# Power_supply.net
KiCad netlist of a schematic drawn in Altium Designer
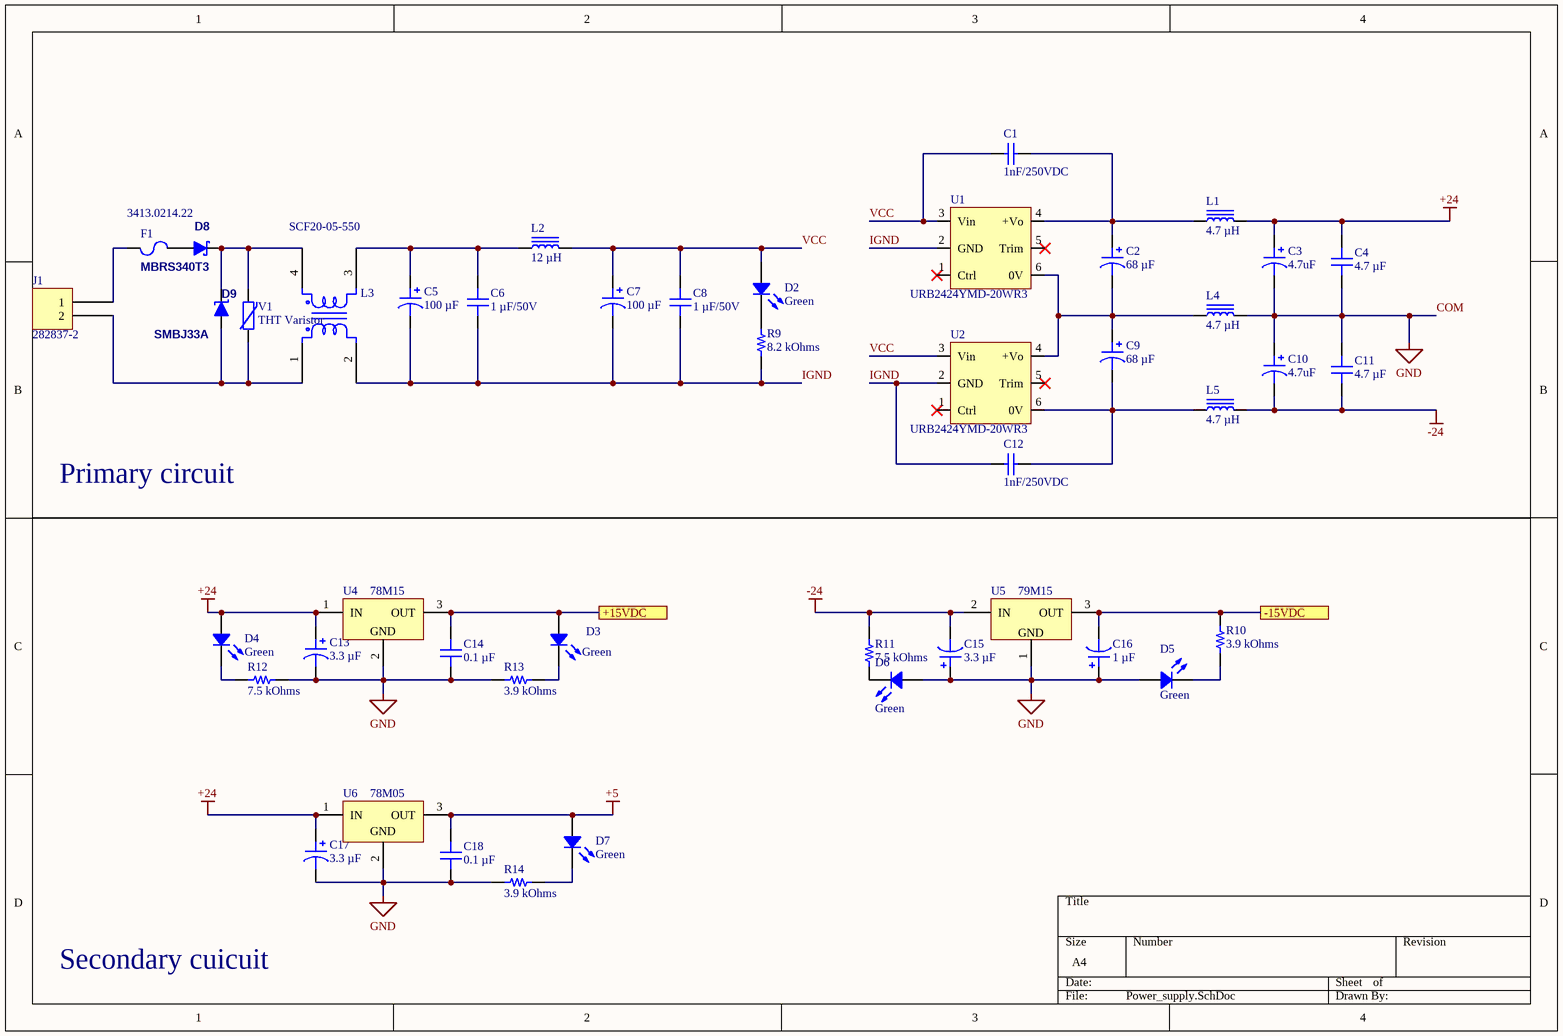
[diagram p0: Power_supply.SchDoc]

(export (version "E")
  (design (tool "Eeschema 10.0.6"))
  (components
    (comp (ref "C1")
      (value "1nF/250VDC")
      (footprint "SIOV-S07K11")
      (description "pitch 7.5 mm")
      (libsource (lib "Capacitor") (part "Y safety capacitor"))
    )
    (comp (ref "C2")
      (value "68 µF")
      (footprint "CAP ALSMD 8.3MM H10.5MM")
      (description "CAP ALUM 68UF 20% 50V SMD")
      (fields (field (name "PART NUMBER") "865060653009") (field (name "MANUFACTURER") "Würth Elektronik"))
      (libsource (lib "Celestial Altium Library - altium_library") (part "Polarised Capacitor"))
    )
    (comp (ref "C3")
      (value "4.7uF")
      (footprint "CAP ALSMD 8.3MM H10.5MM")
      (description "CAP ALUM 47UF 20% 50V SMD")
      (fields (field (name "PART NUMBER") "UCX1H470MCS1GS") (field (name "MANUFACTURER") "Nichicon"))
      (libsource (lib "Celestial Altium Library - altium_library") (part "Polarised Capacitor"))
    )
    (comp (ref "C4")
      (value "4.7 µF")
      (footprint "CAP 1210_3225 - 1MM")
      (description "CAP 1210 X7R 100V 4.7UF 10% 2.50")
      (fields
        (field (name "PART NUMBER") "CNC6P1X7R2A475K250AE")
        (field (name "MANUFACTURER") "TDK Corporation")
      )
      (libsource (lib "Celestial Altium Library - altium_library") (part "Capacitor"))
    )
    (comp (ref "C5")
      (value "100 µF")
      (footprint "CAP ALSMD 8.3MM H10.5MM")
      (description "CAP ALUM 100UF 20% 50V SMD")
      (fields (field (name "PART NUMBER") "UWT1H101MNL1GS") (field (name "MANUFACTURER") "Nichicon"))
      (libsource (lib "Celestial Altium Library - altium_library") (part "Polarised Capacitor"))
    )
    (comp (ref "C6")
      (value "4.7 µF")
      (footprint "CAP 1206_3216 - 0.8MM")
      (description "CAP CER 4.7UF 100V X7S 1206")
      (fields
        (field (name "PART NUMBER") "GRM31CC72A475KE11K")
        (field (name "CAPACITANCE") "1 µF/50V")
        (field (name "MANUFACTURER") "Murata Electronics")
      )
      (libsource (lib "Celestial Altium Library - altium_library") (part "Capacitor"))
    )
    (comp (ref "C7")
      (value "100 µF")
      (footprint "CAP ALSMD 8.3MM H10.5MM")
      (description "CAP ALUM 100UF 20% 50V SMD")
      (fields (field (name "PART NUMBER") "UWT1H101MNL1GS") (field (name "MANUFACTURER") "Nichicon"))
      (libsource (lib "Celestial Altium Library - altium_library") (part "Polarised Capacitor"))
    )
    (comp (ref "C8")
      (value "4.7 µF")
      (footprint "CAP 1206_3216 - 0.8MM")
      (description "CAP CER 4.7UF 100V X7S 1206")
      (fields
        (field (name "PART NUMBER") "GRM31CC72A475KE11K")
        (field (name "CAPACITANCE") "1 µF/50V")
        (field (name "MANUFACTURER") "Murata Electronics")
      )
      (libsource (lib "Celestial Altium Library - altium_library") (part "Capacitor"))
    )
    (comp (ref "C9")
      (value "68 µF")
      (footprint "CAP ALSMD 8.3MM H10.5MM")
      (description "CAP ALUM 68UF 20% 50V SMD")
      (fields (field (name "PART NUMBER") "865060653009") (field (name "MANUFACTURER") "Würth Elektronik"))
      (libsource (lib "Celestial Altium Library - altium_library") (part "Polarised Capacitor"))
    )
    (comp (ref "C10")
      (value "4.7uF")
      (footprint "CAP ALSMD 8.3MM H10.5MM")
      (description "CAP ALUM 47UF 20% 50V SMD")
      (fields (field (name "PART NUMBER") "UCX1H470MCS1GS") (field (name "MANUFACTURER") "Nichicon"))
      (libsource (lib "Celestial Altium Library - altium_library") (part "Polarised Capacitor"))
    )
    (comp (ref "C11")
      (value "4.7 µF")
      (footprint "CAP 1210_3225 - 1MM")
      (description "CAP 1210 X7R 100V 4.7UF 10% 2.50")
      (fields
        (field (name "PART NUMBER") "CNC6P1X7R2A475K250AE")
        (field (name "MANUFACTURER") "TDK Corporation")
      )
      (libsource (lib "Celestial Altium Library - altium_library") (part "Capacitor"))
    )
    (comp (ref "C12")
      (value "1nF/250VDC")
      (footprint "SIOV-S07K11")
      (description "pitch 7.5 mm")
      (libsource (lib "Capacitor") (part "Y safety capacitor"))
    )
    (comp (ref "C13")
      (value "3.3 µF")
      (footprint "CAP ALSMD 4.3MM H5.4MM")
      (description "CAP ALUM 3.3UF 20% 35V SMD")
      (fields
        (field (name "PART NUMBER") "EEE-FC1V3R3R")
        (field (name "MANUFACTURER") "Panasonic Electronic Components")
      )
      (libsource (lib "Celestial Altium Library - altium_library") (part "Polarised Capacitor"))
    )
    (comp (ref "C14")
      (value "0.1 µF")
      (footprint "CAP 0603_1608")
      (description "CAP CER 0.1UF 50V X7R 0603")
      (fields
        (field (name "PART NUMBER") "C0603C104M5RAC7867")
        (field (name "CAPACITANCE") "0.1 µF")
        (field (name "MANUFACTURER") "KEMET")
      )
      (libsource (lib "Celestial Altium Library - altium_library") (part "Capacitor"))
    )
    (comp (ref "C15")
      (value "3.3 µF")
      (footprint "CAP ALSMD 4.3MM H5.4MM")
      (description "CAP ALUM 3.3UF 20% 35V SMD")
      (fields
        (field (name "PART NUMBER") "EEE-FC1V3R3R")
        (field (name "MANUFACTURER") "Panasonic Electronic Components")
      )
      (libsource (lib "Celestial Altium Library - altium_library") (part "Polarised Capacitor"))
    )
    (comp (ref "C16")
      (value "1 µF")
      (footprint "CAP ALSMD 4.3MM H5.4MM")
      (description "CAP ALUM 1UF 20% 50V SMD")
      (fields
        (field (name "PART NUMBER") "EEE-1HA010NR")
        (field (name "MANUFACTURER") "Panasonic Electronic Components")
      )
      (libsource (lib "Celestial Altium Library - altium_library") (part "Polarised Capacitor"))
    )
    (comp (ref "C17")
      (value "3.3 µF")
      (footprint "CAP ALSMD 4.3MM H5.4MM")
      (description "CAP ALUM 3.3UF 20% 35V SMD")
      (fields
        (field (name "PART NUMBER") "EEE-FC1V3R3R")
        (field (name "MANUFACTURER") "Panasonic Electronic Components")
      )
      (libsource (lib "Celestial Altium Library - altium_library") (part "Polarised Capacitor"))
    )
    (comp (ref "C18")
      (value "0.1 µF")
      (footprint "CAP 0603_1608")
      (description "CAP CER 0.1UF 50V X7R 0603")
      (fields
        (field (name "PART NUMBER") "C0603C104M5RAC7867")
        (field (name "CAPACITANCE") "0.1 µF")
        (field (name "MANUFACTURER") "KEMET")
      )
      (libsource (lib "Celestial Altium Library - altium_library") (part "Capacitor"))
    )
    (comp (ref "D2")
      (value "Green")
      (footprint "LED 0603_1608 GREEN")
      (description "LED GREEN CLEAR CHIP 0603 SMD")
      (fields
        (field (name "PART NUMBER") "LSM0603453V")
        (field (name "MANUFACTURER") "Visual Communications Company - VCC")
      )
      (libsource (lib "Celestial Altium Library - altium_library") (part "LED"))
    )
    (comp (ref "D3")
      (value "Green")
      (footprint "LED 0603_1608 GREEN")
      (description "LED GREEN CLEAR CHIP 0603 SMD")
      (fields
        (field (name "PART NUMBER") "LSM0603453V")
        (field (name "MANUFACTURER") "Visual Communications Company - VCC")
      )
      (libsource (lib "Celestial Altium Library - altium_library") (part "LED"))
    )
    (comp (ref "D4")
      (value "Green")
      (footprint "LED 0603_1608 GREEN")
      (description "LED GREEN CLEAR CHIP 0603 SMD")
      (fields
        (field (name "PART NUMBER") "LSM0603453V")
        (field (name "MANUFACTURER") "Visual Communications Company - VCC")
      )
      (libsource (lib "Celestial Altium Library - altium_library") (part "LED"))
    )
    (comp (ref "D5")
      (value "Green")
      (footprint "LED 0603_1608 GREEN")
      (description "LED GREEN CLEAR CHIP 0603 SMD")
      (fields
        (field (name "PART NUMBER") "LSM0603453V")
        (field (name "MANUFACTURER") "Visual Communications Company - VCC")
      )
      (libsource (lib "Celestial Altium Library - altium_library") (part "LED"))
    )
    (comp (ref "D6")
      (value "Green")
      (footprint "LED 0603_1608 GREEN")
      (description "LED GREEN CLEAR CHIP 0603 SMD")
      (fields
        (field (name "PART NUMBER") "LSM0603453V")
        (field (name "MANUFACTURER") "Visual Communications Company - VCC")
      )
      (libsource (lib "Celestial Altium Library - altium_library") (part "LED"))
    )
    (comp (ref "D7")
      (value "Green")
      (footprint "LED 0603_1608 GREEN")
      (description "LED GREEN CLEAR CHIP 0603 SMD")
      (fields
        (field (name "PART NUMBER") "LSM0603453V")
        (field (name "MANUFACTURER") "Visual Communications Company - VCC")
      )
      (libsource (lib "Celestial Altium Library - altium_library") (part "LED"))
    )
    (comp (ref "D8")
      (value "MBRS340T3")
      (footprint "SMC")
      (description "Schottky barrier rectifier: 40V, 3A")
      (libsource (lib "diodes_schottky") (part "MBRS340T3"))
    )
    (comp (ref "D9")
      (value "SMBJ33A")
      (footprint "SMB")
      (description "33V, 600W Surface Mount Transient Voltage Suppression Diode, SMBJ Series")
      (libsource (lib "diodes_transil") (part "SMBJ33A"))
    )
    (comp (ref "F1")
      (value "3413.0214.22")
      (footprint "FUSE 1206_3216 0.6MM")
      (description "FUSE BOARD MNT 630MA 32VAC 63VDC")
      (fields (field (name "MANUFACTURER") "Schurter Inc."))
      (libsource (lib "Celestial Altium Library - altium_library") (part "MOUNTED FUSE"))
    )
    (comp (ref "J1")
      (value "282837-2")
      (footprint "TE 282837-2")
      (description "TERM BLK 2P SIDE ENT 5.08MM PCB")
      (fields (field (name "MANUFACTURER") "TE Connectivity AMP Connectors") (field (name "VOLTAGE") "300 V"))
      (libsource (lib "Celestial Altium Library - altium_library") (part "2 Pin"))
    )
    (comp (ref "L1")
      (value "4.7 µH")
      (footprint "BOURNS SRP5030T")
      (description "FIXED IND 4.7UH 4.6A 53 MOHM SMD")
      (fields (field (name "PART NUMBER") "SRP5030T-4R7M") (field (name "MANUFACTURER") "Bourns Inc."))
      (libsource (lib "Celestial Altium Library - altium_library") (part "Inductor"))
    )
    (comp (ref "L2")
      (value "12 µH")
      (footprint "BOURNS SRR1280")
      (description "FIXED IND 12UH 5.6A 28 MOHM SMD")
      (fields (field (name "PART NUMBER") "SRR1280-120M") (field (name "MANUFACTURER") "Bourns Inc."))
      (libsource (lib "Celestial Altium Library - altium_library") (part "Inductor"))
    )
    (comp (ref "L3")
      (value "SCF20-05-550")
      (footprint "KEMET SCF20-05-550")
      (description "CMC 5.5MH 5A 2LN TH")
      (fields (field (name "MANUFACTURER") "KEMET"))
      (libsource (lib "Celestial Altium Library - altium_library") (part "KEMET SCF"))
    )
    (comp (ref "L4")
      (value "4.7 µH")
      (footprint "BOURNS SRP5030T")
      (description "FIXED IND 4.7UH 4.6A 53 MOHM SMD")
      (fields (field (name "PART NUMBER") "SRP5030T-4R7M") (field (name "MANUFACTURER") "Bourns Inc."))
      (libsource (lib "Celestial Altium Library - altium_library") (part "Inductor"))
    )
    (comp (ref "L5")
      (value "4.7 µH")
      (footprint "BOURNS SRP5030T")
      (description "FIXED IND 4.7UH 4.6A 53 MOHM SMD")
      (fields (field (name "PART NUMBER") "SRP5030T-4R7M") (field (name "MANUFACTURER") "Bourns Inc."))
      (libsource (lib "Celestial Altium Library - altium_library") (part "Inductor"))
    )
    (comp (ref "R9")
      (value "8.2 kOhms")
      (footprint "RES 0805_2012")
      (description "RES SMD 8.2K OHM 0.5% 1/4W 0805")
      (fields
        (field (name "PART NUMBER") "ERJ-PB6D8201V")
        (field (name "MANUFACTURER") "Panasonic Electronic Components")
      )
      (libsource (lib "Celestial Altium Library - altium_library") (part "Resistor"))
    )
    (comp (ref "R10")
      (value "3.9 kOhms")
      (footprint "RES 0805_2012")
      (description "RES 3.9K OHM 1% 1/3W 0805")
      (fields
        (field (name "PART NUMBER") "CRGP0805F3K9")
        (field (name "MANUFACTURER") "TE Connectivity Passive Product")
      )
      (libsource (lib "Celestial Altium Library - altium_library") (part "Resistor"))
    )
    (comp (ref "R11")
      (value "7.5 kOhms")
      (footprint "RES 0805_2012")
      (description "RES SMD 7.5K OHM 0.1% 1/10W 0805")
      (fields
        (field (name "PART NUMBER") "RN73C2A7K5BTDF")
        (field (name "MANUFACTURER") "TE Connectivity Passive Product")
      )
      (libsource (lib "Celestial Altium Library - altium_library") (part "Resistor"))
    )
    (comp (ref "R12")
      (value "7.5 kOhms")
      (footprint "RES 0805_2012")
      (description "RES SMD 7.5K OHM 0.1% 1/10W 0805")
      (fields
        (field (name "PART NUMBER") "RN73C2A7K5BTDF")
        (field (name "MANUFACTURER") "TE Connectivity Passive Product")
      )
      (libsource (lib "Celestial Altium Library - altium_library") (part "Resistor"))
    )
    (comp (ref "R13")
      (value "3.9 kOhms")
      (footprint "RES 0805_2012")
      (description "RES 3.9K OHM 1% 1/3W 0805")
      (fields
        (field (name "PART NUMBER") "CRGP0805F3K9")
        (field (name "MANUFACTURER") "TE Connectivity Passive Product")
      )
      (libsource (lib "Celestial Altium Library - altium_library") (part "Resistor"))
    )
    (comp (ref "R14")
      (value "3.9 kOhms")
      (footprint "RES 0805_2012")
      (description "RES 3.9K OHM 1% 1/3W 0805")
      (fields
        (field (name "PART NUMBER") "CRGP0805F3K9")
        (field (name "MANUFACTURER") "TE Connectivity Passive Product")
      )
      (libsource (lib "Celestial Altium Library - altium_library") (part "Resistor"))
    )
    (comp (ref "U1")
      (value "URB2424YMD-20WR3")
      (footprint "URB_YMD-20WR3")
      (description "Isolated DC-DC Converter")
      (libsource (lib "URB2424YMD-20WR3") (part "URB_YMD-20WR3"))
    )
    (comp (ref "U2")
      (value "URB2424YMD-20WR3")
      (footprint "URB_YMD-20WR3")
      (description "Isolated DC-DC Converter")
      (libsource (lib "URB2424YMD-20WR3") (part "URB_YMD-20WR3"))
    )
    (comp (ref "U4")
      (value "78M15")
      (footprint "TO252")
      (description "SMD")
      (libsource (lib "IC") (part "78M15"))
    )
    (comp (ref "U5")
      (value "79M15")
      (footprint "TO252")
      (description "SMD")
      (libsource (lib "IC") (part "79M15"))
    )
    (comp (ref "U6")
      (value "78M05")
      (footprint "TO252")
      (description "SMD")
      (libsource (lib "IC") (part "78M05"))
    )
    (comp (ref "V1")
      (value "THT Varistor")
      (footprint "SIOV-S07K11")
      (libsource (lib "varistors") (part "VaristorTHT"))
    )
  )
  (nets
    (net (code "1") (name "+5") (class "Default")
      (node (ref "C18") (pin "2") (pinfunction "2_2") (pintype "passive"))
      (node (ref "D7") (pin "1") (pinfunction "1_1") (pintype "passive"))
      (node (ref "U6") (pin "3") (pinfunction "OUT_3") (pintype "power_in"))
    )
    (net (code "2") (name "+24") (class "Default")
      (node (ref "C13") (pin "1") (pinfunction "1_1") (pintype "passive"))
      (node (ref "C17") (pin "1") (pinfunction "1_1") (pintype "passive"))
      (node (ref "C3") (pin "1") (pinfunction "1_1") (pintype "passive"))
      (node (ref "C4") (pin "2") (pinfunction "2_2") (pintype "passive"))
      (node (ref "D4") (pin "1") (pinfunction "1_1") (pintype "passive"))
      (node (ref "L1") (pin "2") (pinfunction "2_2") (pintype "passive"))
      (node (ref "U4") (pin "1") (pinfunction "IN_1") (pintype "power_in"))
      (node (ref "U6") (pin "1") (pinfunction "IN_1") (pintype "power_in"))
    )
    (net (code "3") (name "-24") (class "Default")
      (node (ref "C10") (pin "2") (pinfunction "2_2") (pintype "passive"))
      (node (ref "C11") (pin "1") (pinfunction "1_1") (pintype "passive"))
      (node (ref "C15") (pin "2") (pinfunction "2_2") (pintype "passive"))
      (node (ref "L5") (pin "2") (pinfunction "2_2") (pintype "passive"))
      (node (ref "R11") (pin "2") (pinfunction "2_2") (pintype "passive"))
      (node (ref "U5") (pin "2") (pinfunction "IN_2") (pintype "power_in"))
    )
    (net (code "4") (name "/+15VDC") (class "Default")
      (node (ref "C14") (pin "2") (pinfunction "2_2") (pintype "passive"))
      (node (ref "D3") (pin "1") (pinfunction "1_1") (pintype "passive"))
      (node (ref "U4") (pin "3") (pinfunction "OUT_3") (pintype "power_in"))
    )
    (net (code "5") (name "/-15VDC") (class "Default")
      (node (ref "C16") (pin "2") (pinfunction "2_2") (pintype "passive"))
      (node (ref "R10") (pin "2") (pinfunction "2_2") (pintype "passive"))
      (node (ref "U5") (pin "3") (pinfunction "OUT_3") (pintype "power_in"))
    )
    (net (code "6") (name "/IGND") (class "Default")
      (node (ref "C12") (pin "2") (pinfunction "2_2") (pintype "passive"))
      (node (ref "C5") (pin "2") (pinfunction "2_2") (pintype "passive"))
      (node (ref "C6") (pin "1") (pinfunction "1_1") (pintype "passive"))
      (node (ref "C7") (pin "2") (pinfunction "2_2") (pintype "passive"))
      (node (ref "C8") (pin "1") (pinfunction "1_1") (pintype "passive"))
      (node (ref "L3") (pin "2") (pinfunction "2_2") (pintype "passive"))
      (node (ref "R9") (pin "1") (pinfunction "1_1") (pintype "passive"))
      (node (ref "U1") (pin "2") (pinfunction "GND_2") (pintype "passive"))
      (node (ref "U2") (pin "2") (pinfunction "GND_2") (pintype "passive"))
    )
    (net (code "7") (name "/VCC") (class "Default")
      (node (ref "C1") (pin "2") (pinfunction "2_2") (pintype "passive"))
      (node (ref "C7") (pin "1") (pinfunction "1_1") (pintype "passive"))
      (node (ref "C8") (pin "2") (pinfunction "2_2") (pintype "passive"))
      (node (ref "D2") (pin "1") (pinfunction "1_1") (pintype "passive"))
      (node (ref "L2") (pin "2") (pinfunction "2_2") (pintype "passive"))
      (node (ref "U1") (pin "3") (pinfunction "Vin_3") (pintype "passive"))
      (node (ref "U2") (pin "3") (pinfunction "Vin_3") (pintype "passive"))
    )
    (net (code "8") (name "GND") (class "Default")
      (node (ref "C10") (pin "1") (pinfunction "1_1") (pintype "passive"))
      (node (ref "C11") (pin "2") (pinfunction "2_2") (pintype "passive"))
      (node (ref "C13") (pin "2") (pinfunction "2_2") (pintype "passive"))
      (node (ref "C14") (pin "1") (pinfunction "1_1") (pintype "passive"))
      (node (ref "C15") (pin "1") (pinfunction "1_1") (pintype "passive"))
      (node (ref "C16") (pin "1") (pinfunction "1_1") (pintype "passive"))
      (node (ref "C17") (pin "2") (pinfunction "2_2") (pintype "passive"))
      (node (ref "C18") (pin "1") (pinfunction "1_1") (pintype "passive"))
      (node (ref "C3") (pin "2") (pinfunction "2_2") (pintype "passive"))
      (node (ref "C4") (pin "1") (pinfunction "1_1") (pintype "passive"))
      (node (ref "D5") (pin "1") (pinfunction "1_1") (pintype "passive"))
      (node (ref "D6") (pin "1") (pinfunction "1_1") (pintype "passive"))
      (node (ref "L4") (pin "2") (pinfunction "2_2") (pintype "passive"))
      (node (ref "R12") (pin "2") (pinfunction "2_2") (pintype "passive"))
      (node (ref "R13") (pin "1") (pinfunction "1_1") (pintype "passive"))
      (node (ref "R14") (pin "1") (pinfunction "1_1") (pintype "passive"))
      (node (ref "U4") (pin "2") (pinfunction "GND_2") (pintype "power_in"))
      (node (ref "U5") (pin "1") (pinfunction "GND_1") (pintype "power_in"))
      (node (ref "U6") (pin "2") (pinfunction "GND_2") (pintype "power_in"))
    )
    (net (code "9") (name "Net-(C5-Pad1)") (class "Default")
      (node (ref "C5") (pin "1") (pinfunction "1_1") (pintype "passive"))
      (node (ref "C6") (pin "2") (pinfunction "2_2") (pintype "passive"))
      (node (ref "L2") (pin "1") (pinfunction "1_1") (pintype "passive"))
      (node (ref "L3") (pin "3") (pinfunction "3_3") (pintype "passive"))
    )
    (net (code "10") (name "Net-(D2-Pad2)") (class "Default")
      (node (ref "D2") (pin "2") (pinfunction "2_2") (pintype "passive"))
      (node (ref "R9") (pin "2") (pinfunction "2_2") (pintype "passive"))
    )
    (net (code "11") (name "Net-(D3-Pad2)") (class "Default")
      (node (ref "D3") (pin "2") (pinfunction "2_2") (pintype "passive"))
      (node (ref "R13") (pin "2") (pinfunction "2_2") (pintype "passive"))
    )
    (net (code "12") (name "Net-(D4-Pad2)") (class "Default")
      (node (ref "D4") (pin "2") (pinfunction "2_2") (pintype "passive"))
      (node (ref "R12") (pin "1") (pinfunction "1_1") (pintype "passive"))
    )
    (net (code "13") (name "Net-(D5-Pad2)") (class "Default")
      (node (ref "D5") (pin "2") (pinfunction "2_2") (pintype "passive"))
      (node (ref "R10") (pin "1") (pinfunction "1_1") (pintype "passive"))
    )
    (net (code "14") (name "Net-(D6-Pad2)") (class "Default")
      (node (ref "D6") (pin "2") (pinfunction "2_2") (pintype "passive"))
      (node (ref "R11") (pin "1") (pinfunction "1_1") (pintype "passive"))
    )
    (net (code "15") (name "Net-(D7-Pad2)") (class "Default")
      (node (ref "D7") (pin "2") (pinfunction "2_2") (pintype "passive"))
      (node (ref "R14") (pin "2") (pinfunction "2_2") (pintype "passive"))
    )
    (net (code "16") (name "Net-(D8-A)") (class "Default")
      (node (ref "D8") (pin "1") (pinfunction "A_1") (pintype "passive"))
      (node (ref "F1") (pin "2") (pintype "passive"))
    )
    (net (code "17") (name "Net-(D8-K)") (class "Default")
      (node (ref "D8") (pin "2") (pinfunction "K_2") (pintype "passive"))
      (node (ref "D9") (pin "2") (pinfunction "K_2") (pintype "passive"))
      (node (ref "L3") (pin "4") (pinfunction "4_4") (pintype "passive"))
      (node (ref "V1") (pin "2") (pinfunction "2_2") (pintype "passive"))
    )
    (net (code "18") (name "Net-(D9-A)") (class "Default")
      (node (ref "D9") (pin "1") (pinfunction "A_1") (pintype "passive"))
      (node (ref "J1") (pin "2") (pinfunction "2_2") (pintype "passive"))
      (node (ref "L3") (pin "1") (pinfunction "1_1") (pintype "passive"))
      (node (ref "V1") (pin "1") (pinfunction "1_1") (pintype "passive"))
    )
    (net (code "19") (name "Net-(F1-Pad1)") (class "Default")
      (node (ref "F1") (pin "1") (pintype "passive"))
      (node (ref "J1") (pin "1") (pinfunction "1_1") (pintype "passive"))
    )
    (net (code "20") (name "Net-(U1-+Vo)") (class "Default")
      (node (ref "C1") (pin "1") (pinfunction "1_1") (pintype "passive"))
      (node (ref "C2") (pin "1") (pinfunction "1_1") (pintype "passive"))
      (node (ref "L1") (pin "1") (pinfunction "1_1") (pintype "passive"))
      (node (ref "U1") (pin "4") (pinfunction "+Vo_4") (pintype "passive"))
    )
    (net (code "21") (name "Net-(U1-0V)") (class "Default")
      (node (ref "C2") (pin "2") (pinfunction "2_2") (pintype "passive"))
      (node (ref "C9") (pin "1") (pinfunction "1_1") (pintype "passive"))
      (node (ref "L4") (pin "1") (pinfunction "1_1") (pintype "passive"))
      (node (ref "U1") (pin "6") (pinfunction "0V_6") (pintype "passive"))
      (node (ref "U2") (pin "4") (pinfunction "+Vo_4") (pintype "passive"))
    )
    (net (code "22") (name "Net-(U2-0V)") (class "Default")
      (node (ref "C12") (pin "1") (pinfunction "1_1") (pintype "passive"))
      (node (ref "C9") (pin "2") (pinfunction "2_2") (pintype "passive"))
      (node (ref "L5") (pin "1") (pinfunction "1_1") (pintype "passive"))
      (node (ref "U2") (pin "6") (pinfunction "0V_6") (pintype "passive"))
    )
    (net (code "23") (name "unconnected-(U1-Ctrl-Pad1)") (class "Default")
      (node (ref "U1") (pin "1") (pinfunction "Ctrl_1") (pintype "passive+no_connect"))
    )
    (net (code "24") (name "unconnected-(U1-Trim-Pad5)") (class "Default")
      (node (ref "U1") (pin "5") (pinfunction "Trim_5") (pintype "passive+no_connect"))
    )
    (net (code "25") (name "unconnected-(U2-Ctrl-Pad1)") (class "Default")
      (node (ref "U2") (pin "1") (pinfunction "Ctrl_1") (pintype "passive+no_connect"))
    )
    (net (code "26") (name "unconnected-(U2-Trim-Pad5)") (class "Default")
      (node (ref "U2") (pin "5") (pinfunction "Trim_5") (pintype "passive+no_connect"))
    )
  )
)
